# fps_revc.net
KiCad netlist of a schematic drawn in EAGLE
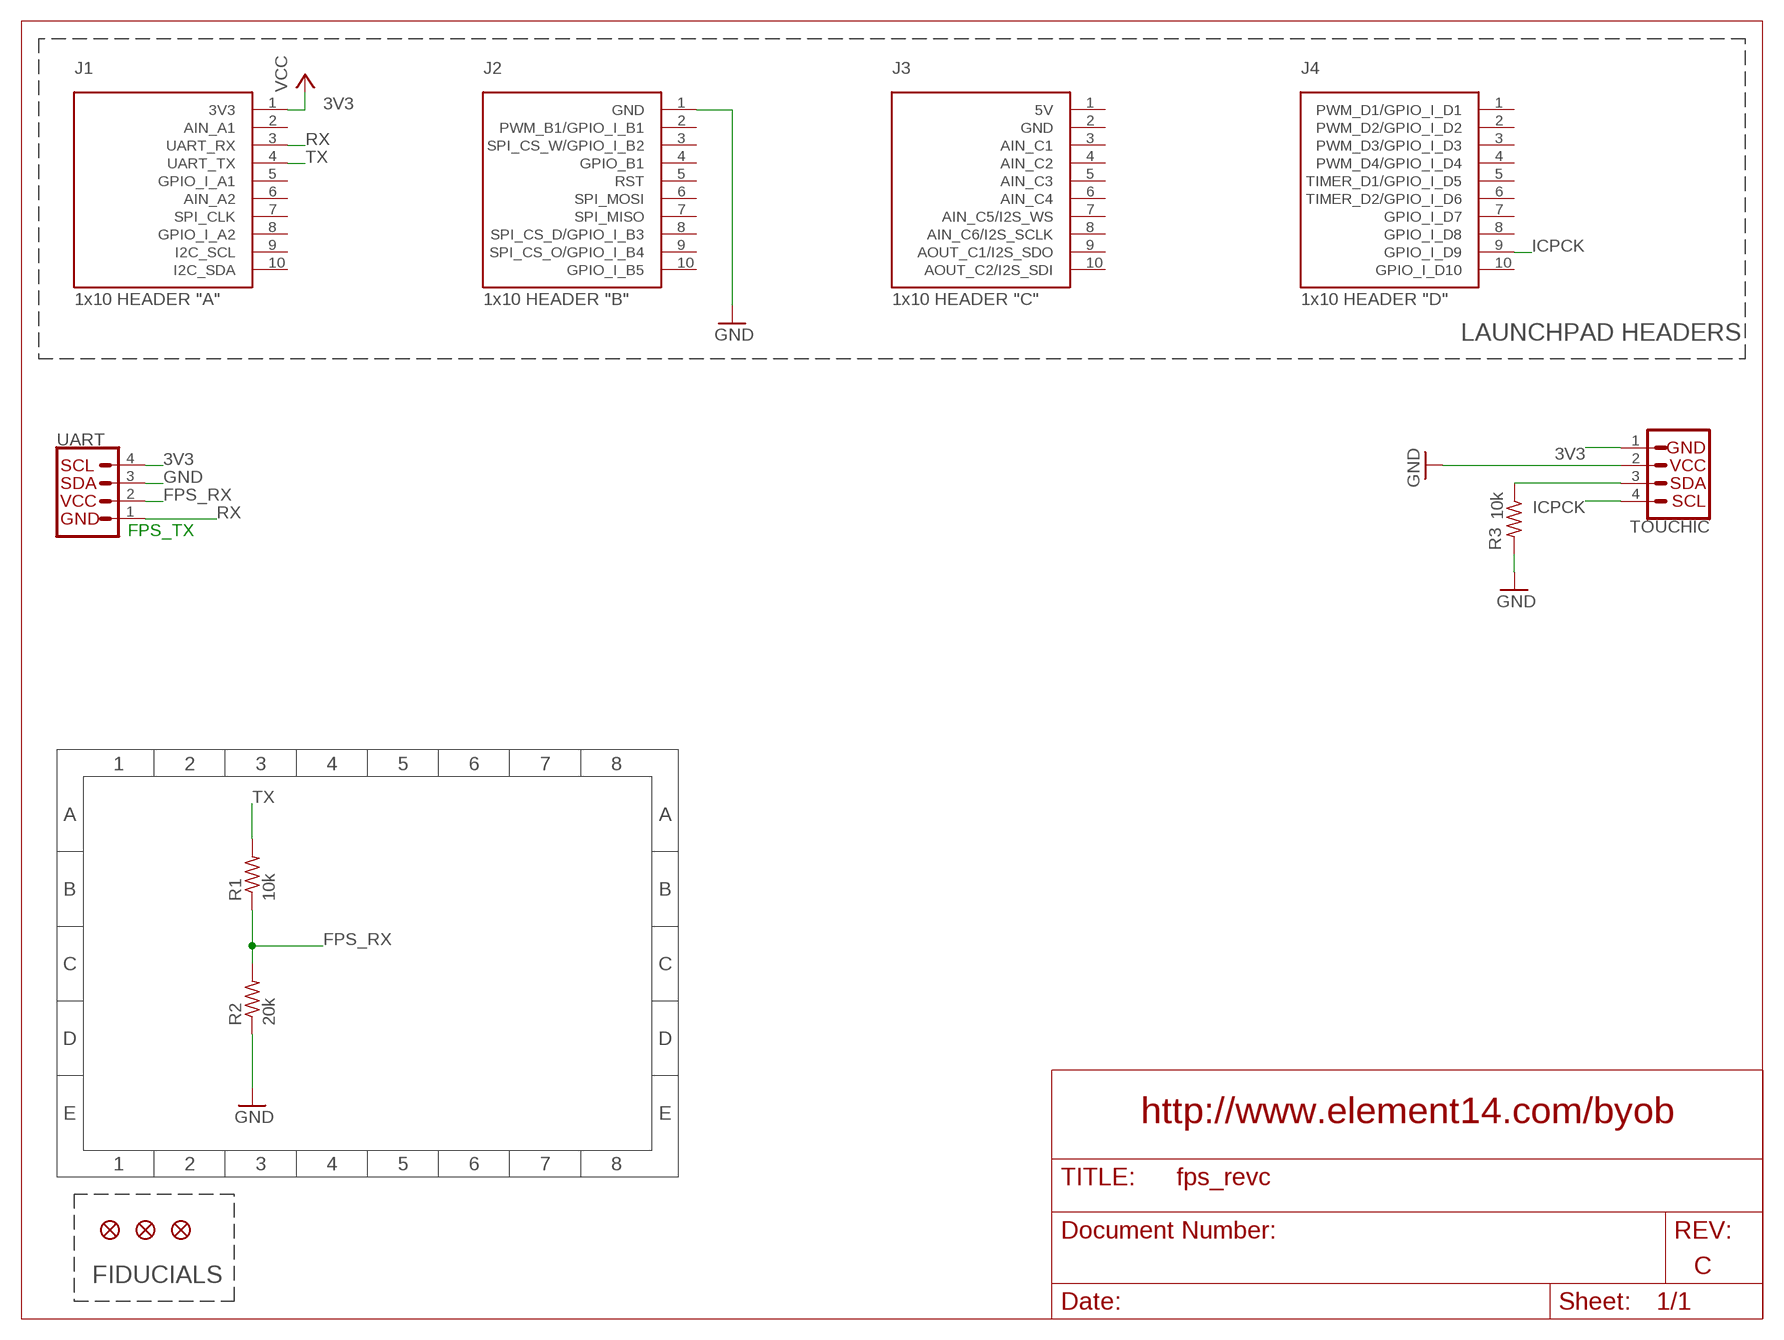
[diagram p0: schematic, sheet 1]

(export (version "E")
  (design (tool "Eeschema 10.0.6"))
  (components
    (comp (ref "FID1")
      (value "FIDUCIAL")
      (footprint "eagle-import:FIDUCIAL_L10")
      (libsource (lib "eagle-import") (part "FIDUCIAL"))
    )
    (comp (ref "FID2")
      (value "FIDUCIAL")
      (footprint "eagle-import:FIDUCIAL_L10")
      (libsource (lib "eagle-import") (part "FIDUCIAL"))
    )
    (comp (ref "FID3")
      (value "FIDUCIAL")
      (footprint "eagle-import:FIDUCIAL_L10")
      (libsource (lib "eagle-import") (part "FIDUCIAL"))
    )
    (comp (ref "J1")
      (value "1x10 HEADER \"A\"")
      (footprint "eagle-import:1X10")
      (fields (field (name "MF") "SAMTEC") (field (name "MPN") "SSW-110-23-F-D"))
      (libsource (lib "eagle-import") (part "HEADER-1X10-J1"))
    )
    (comp (ref "J2")
      (value "1x10 HEADER \"B\"")
      (footprint "eagle-import:1X10")
      (fields (field (name "MF") "SAMTEC") (field (name "MPN") "SSW-110-23-F-D"))
      (libsource (lib "eagle-import") (part "HEADER-1X10-J2"))
    )
    (comp (ref "J3")
      (value "1x10 HEADER \"C\"")
      (footprint "eagle-import:1X10")
      (libsource (lib "eagle-import") (part "HEADER-1X10-J3"))
    )
    (comp (ref "J4")
      (value "1x10 HEADER \"D\"")
      (footprint "eagle-import:1X10")
      (libsource (lib "eagle-import") (part "HEADER-1X10-J4"))
    )
    (comp (ref "R1")
      (value "10k")
      (footprint "eagle-import:R0805")
      (fields (field (name "MF") "PANASONIC") (field (name "MPN") "ERJ6GEYJ103V"))
      (libsource (lib "eagle-import") (part "R-US_R0805"))
    )
    (comp (ref "R2")
      (value "20k")
      (footprint "eagle-import:R0805")
      (fields (field (name "MF") "VISHAY") (field (name "MPN") "CRCW080520K0FKEB"))
      (libsource (lib "eagle-import") (part "R-US_R0805"))
    )
    (comp (ref "R3")
      (value "10k")
      (footprint "eagle-import:R0805")
      (fields (field (name "MF") "PANASONIC") (field (name "MPN") "ERJ6GEYJ103V"))
      (libsource (lib "eagle-import") (part "R-US_R0805"))
    )
    (comp (ref "TOUCHIC")
      (value "QWIIC_CONNECTORJS-1MM")
      (footprint "eagle-import:1X04_1MM_RA")
      (fields
        (field (name "MF") "JST (JAPAN SOLDERLESS TERMINALS)")
        (field (name "MPN") "SM04B-SRSS-TB(LF)(SN)")
      )
      (libsource (lib "eagle-import") (part "QWIIC_CONNECTORJS-1MM"))
    )
    (comp (ref "UART")
      (value "QWIIC_CONNECTORJS-1MM")
      (footprint "eagle-import:1X04_1MM_RA")
      (fields
        (field (name "MF") "JST (JAPAN SOLDERLESS TERMINALS)")
        (field (name "MPN") "SM04B-SRSS-TB(LF)(SN)")
      )
      (libsource (lib "eagle-import") (part "QWIIC_CONNECTORJS-1MM"))
    )
  )
  (nets
    (net (code "1") (name "/FPS_RX") (class "Default")
      (node (ref "R1") (pin "1") (pinfunction "1_1") (pintype "passive"))
      (node (ref "R2") (pin "2") (pinfunction "2_2") (pintype "passive"))
      (node (ref "UART") (pin "2") (pinfunction "VCC_2") (pintype "power_in"))
    )
    (net (code "2") (name "/ICPCK") (class "Default")
      (node (ref "J4") (pin "9") (pinfunction "GPIO_I_D9_9") (pintype "bidirectional"))
      (node (ref "TOUCHIC") (pin "4") (pinfunction "SCL_4") (pintype "passive"))
    )
    (net (code "3") (name "/RX") (class "Default")
      (node (ref "J1") (pin "3") (pinfunction "UART_RX_3") (pintype "bidirectional"))
      (node (ref "UART") (pin "1") (pinfunction "GND_1") (pintype "power_in"))
    )
    (net (code "4") (name "/TX") (class "Default")
      (node (ref "J1") (pin "4") (pinfunction "UART_TX_4") (pintype "bidirectional"))
      (node (ref "R1") (pin "2") (pinfunction "2_2") (pintype "passive"))
    )
    (net (code "5") (name "GND") (class "Default")
      (node (ref "J2") (pin "1") (pinfunction "GND_1") (pintype "bidirectional"))
      (node (ref "R2") (pin "1") (pinfunction "1_1") (pintype "passive"))
      (node (ref "R3") (pin "2") (pinfunction "2_2") (pintype "passive"))
      (node (ref "TOUCHIC") (pin "2") (pinfunction "VCC_2") (pintype "power_in"))
      (node (ref "UART") (pin "3") (pinfunction "SDA_3") (pintype "passive"))
    )
    (net (code "6") (name "Net-(TOUCHIC-SDA)") (class "Default")
      (node (ref "R3") (pin "1") (pinfunction "1_1") (pintype "passive"))
      (node (ref "TOUCHIC") (pin "3") (pinfunction "SDA_3") (pintype "passive"))
    )
    (net (code "7") (name "VCC") (class "Default")
      (node (ref "J1") (pin "1") (pinfunction "3V3_1") (pintype "bidirectional"))
      (node (ref "TOUCHIC") (pin "1") (pinfunction "GND_1") (pintype "power_in"))
      (node (ref "UART") (pin "4") (pinfunction "SCL_4") (pintype "passive"))
    )
    (net (code "8") (name "unconnected-(J1-AIN_A1-Pad2)") (class "Default")
      (node (ref "J1") (pin "2") (pinfunction "AIN_A1_2") (pintype "bidirectional"))
    )
    (net (code "9") (name "unconnected-(J1-AIN_A2-Pad6)") (class "Default")
      (node (ref "J1") (pin "6") (pinfunction "AIN_A2_6") (pintype "bidirectional"))
    )
    (net (code "10") (name "unconnected-(J1-GPIO_I_A1-Pad5)") (class "Default")
      (node (ref "J1") (pin "5") (pinfunction "GPIO_I_A1_5") (pintype "bidirectional"))
    )
    (net (code "11") (name "unconnected-(J1-GPIO_I_A2-Pad8)") (class "Default")
      (node (ref "J1") (pin "8") (pinfunction "GPIO_I_A2_8") (pintype "bidirectional"))
    )
    (net (code "12") (name "unconnected-(J1-I2C_SCL-Pad9)") (class "Default")
      (node (ref "J1") (pin "9") (pinfunction "I2C_SCL_9") (pintype "bidirectional"))
    )
    (net (code "13") (name "unconnected-(J1-I2C_SDA-Pad10)") (class "Default")
      (node (ref "J1") (pin "10") (pinfunction "I2C_SDA_10") (pintype "bidirectional"))
    )
    (net (code "14") (name "unconnected-(J1-SPI_CLK-Pad7)") (class "Default")
      (node (ref "J1") (pin "7") (pinfunction "SPI_CLK_7") (pintype "bidirectional"))
    )
    (net (code "15") (name "unconnected-(J2-GPIO_B1-Pad4)") (class "Default")
      (node (ref "J2") (pin "4") (pinfunction "GPIO_B1_4") (pintype "bidirectional"))
    )
    (net (code "16") (name "unconnected-(J2-GPIO_I_B5-Pad10)") (class "Default")
      (node (ref "J2") (pin "10") (pinfunction "GPIO_I_B5_10") (pintype "bidirectional"))
    )
    (net (code "17") (name "unconnected-(J2-PWM_B1{slash}GPIO_I_B1-Pad2)") (class "Default")
      (node (ref "J2") (pin "2") (pinfunction "PWM_B1/GPIO_I_B1_2") (pintype "bidirectional"))
    )
    (net (code "18") (name "unconnected-(J2-RST-Pad5)") (class "Default")
      (node (ref "J2") (pin "5") (pinfunction "RST_5") (pintype "bidirectional"))
    )
    (net (code "19") (name "unconnected-(J2-SPI_CS_D{slash}GPIO_I_B3-Pad8)") (class "Default")
      (node (ref "J2") (pin "8") (pinfunction "SPI_CS_D/GPIO_I_B3_8") (pintype "bidirectional"))
    )
    (net (code "20") (name "unconnected-(J2-SPI_CS_O{slash}GPIO_I_B4-Pad9)") (class "Default")
      (node (ref "J2") (pin "9") (pinfunction "SPI_CS_O/GPIO_I_B4_9") (pintype "bidirectional"))
    )
    (net (code "21") (name "unconnected-(J2-SPI_CS_W{slash}GPIO_I_B2-Pad3)") (class "Default")
      (node (ref "J2") (pin "3") (pinfunction "SPI_CS_W/GPIO_I_B2_3") (pintype "bidirectional"))
    )
    (net (code "22") (name "unconnected-(J2-SPI_MISO-Pad7)") (class "Default")
      (node (ref "J2") (pin "7") (pinfunction "SPI_MISO_7") (pintype "bidirectional"))
    )
    (net (code "23") (name "unconnected-(J2-SPI_MOSI-Pad6)") (class "Default")
      (node (ref "J2") (pin "6") (pinfunction "SPI_MOSI_6") (pintype "bidirectional"))
    )
    (net (code "24") (name "unconnected-(J3-5V-Pad1)") (class "Default")
      (node (ref "J3") (pin "1") (pinfunction "5V_1") (pintype "bidirectional"))
    )
    (net (code "25") (name "unconnected-(J3-AIN_C1-Pad3)") (class "Default")
      (node (ref "J3") (pin "3") (pinfunction "AIN_C1_3") (pintype "bidirectional"))
    )
    (net (code "26") (name "unconnected-(J3-AIN_C2-Pad4)") (class "Default")
      (node (ref "J3") (pin "4") (pinfunction "AIN_C2_4") (pintype "bidirectional"))
    )
    (net (code "27") (name "unconnected-(J3-AIN_C3-Pad5)") (class "Default")
      (node (ref "J3") (pin "5") (pinfunction "AIN_C3_5") (pintype "bidirectional"))
    )
    (net (code "28") (name "unconnected-(J3-AIN_C4-Pad6)") (class "Default")
      (node (ref "J3") (pin "6") (pinfunction "AIN_C4_6") (pintype "bidirectional"))
    )
    (net (code "29") (name "unconnected-(J3-AIN_C5{slash}I2S_WS-Pad7)") (class "Default")
      (node (ref "J3") (pin "7") (pinfunction "AIN_C5/I2S_WS_7") (pintype "bidirectional"))
    )
    (net (code "30") (name "unconnected-(J3-AIN_C6{slash}I2S_SCLK-Pad8)") (class "Default")
      (node (ref "J3") (pin "8") (pinfunction "AIN_C6/I2S_SCLK_8") (pintype "bidirectional"))
    )
    (net (code "31") (name "unconnected-(J3-AOUT_C1{slash}I2S_SDO-Pad9)") (class "Default")
      (node (ref "J3") (pin "9") (pinfunction "AOUT_C1/I2S_SDO_9") (pintype "bidirectional"))
    )
    (net (code "32") (name "unconnected-(J3-AOUT_C2{slash}I2S_SDI-Pad10)") (class "Default")
      (node (ref "J3") (pin "10") (pinfunction "AOUT_C2/I2S_SDI_10") (pintype "bidirectional"))
    )
    (net (code "33") (name "unconnected-(J3-GND-Pad2)") (class "Default")
      (node (ref "J3") (pin "2") (pinfunction "GND_2") (pintype "bidirectional"))
    )
    (net (code "34") (name "unconnected-(J4-GPIO_I_D7-Pad7)") (class "Default")
      (node (ref "J4") (pin "7") (pinfunction "GPIO_I_D7_7") (pintype "bidirectional"))
    )
    (net (code "35") (name "unconnected-(J4-GPIO_I_D8-Pad8)") (class "Default")
      (node (ref "J4") (pin "8") (pinfunction "GPIO_I_D8_8") (pintype "bidirectional"))
    )
    (net (code "36") (name "unconnected-(J4-GPIO_I_D10-Pad10)") (class "Default")
      (node (ref "J4") (pin "10") (pinfunction "GPIO_I_D10_10") (pintype "bidirectional"))
    )
    (net (code "37") (name "unconnected-(J4-PWM_D1{slash}GPIO_I_D1-Pad1)") (class "Default")
      (node (ref "J4") (pin "1") (pinfunction "PWM_D1/GPIO_I_D1_1") (pintype "bidirectional"))
    )
    (net (code "38") (name "unconnected-(J4-PWM_D2{slash}GPIO_I_D2-Pad2)") (class "Default")
      (node (ref "J4") (pin "2") (pinfunction "PWM_D2/GPIO_I_D2_2") (pintype "bidirectional"))
    )
    (net (code "39") (name "unconnected-(J4-PWM_D3{slash}GPIO_I_D3-Pad3)") (class "Default")
      (node (ref "J4") (pin "3") (pinfunction "PWM_D3/GPIO_I_D3_3") (pintype "bidirectional"))
    )
    (net (code "40") (name "unconnected-(J4-PWM_D4{slash}GPIO_I_D4-Pad4)") (class "Default")
      (node (ref "J4") (pin "4") (pinfunction "PWM_D4/GPIO_I_D4_4") (pintype "bidirectional"))
    )
    (net (code "41") (name "unconnected-(J4-TIMER_D1{slash}GPIO_I_D5-Pad5)") (class "Default")
      (node (ref "J4") (pin "5") (pinfunction "TIMER_D1/GPIO_I_D5_5") (pintype "bidirectional"))
    )
    (net (code "42") (name "unconnected-(J4-TIMER_D2{slash}GPIO_I_D6-Pad6)") (class "Default")
      (node (ref "J4") (pin "6") (pinfunction "TIMER_D2/GPIO_I_D6_6") (pintype "bidirectional"))
    )
  )
)
